# F28335_Level_Shifters.net
KiCad netlist of a schematic drawn in Altium Designer
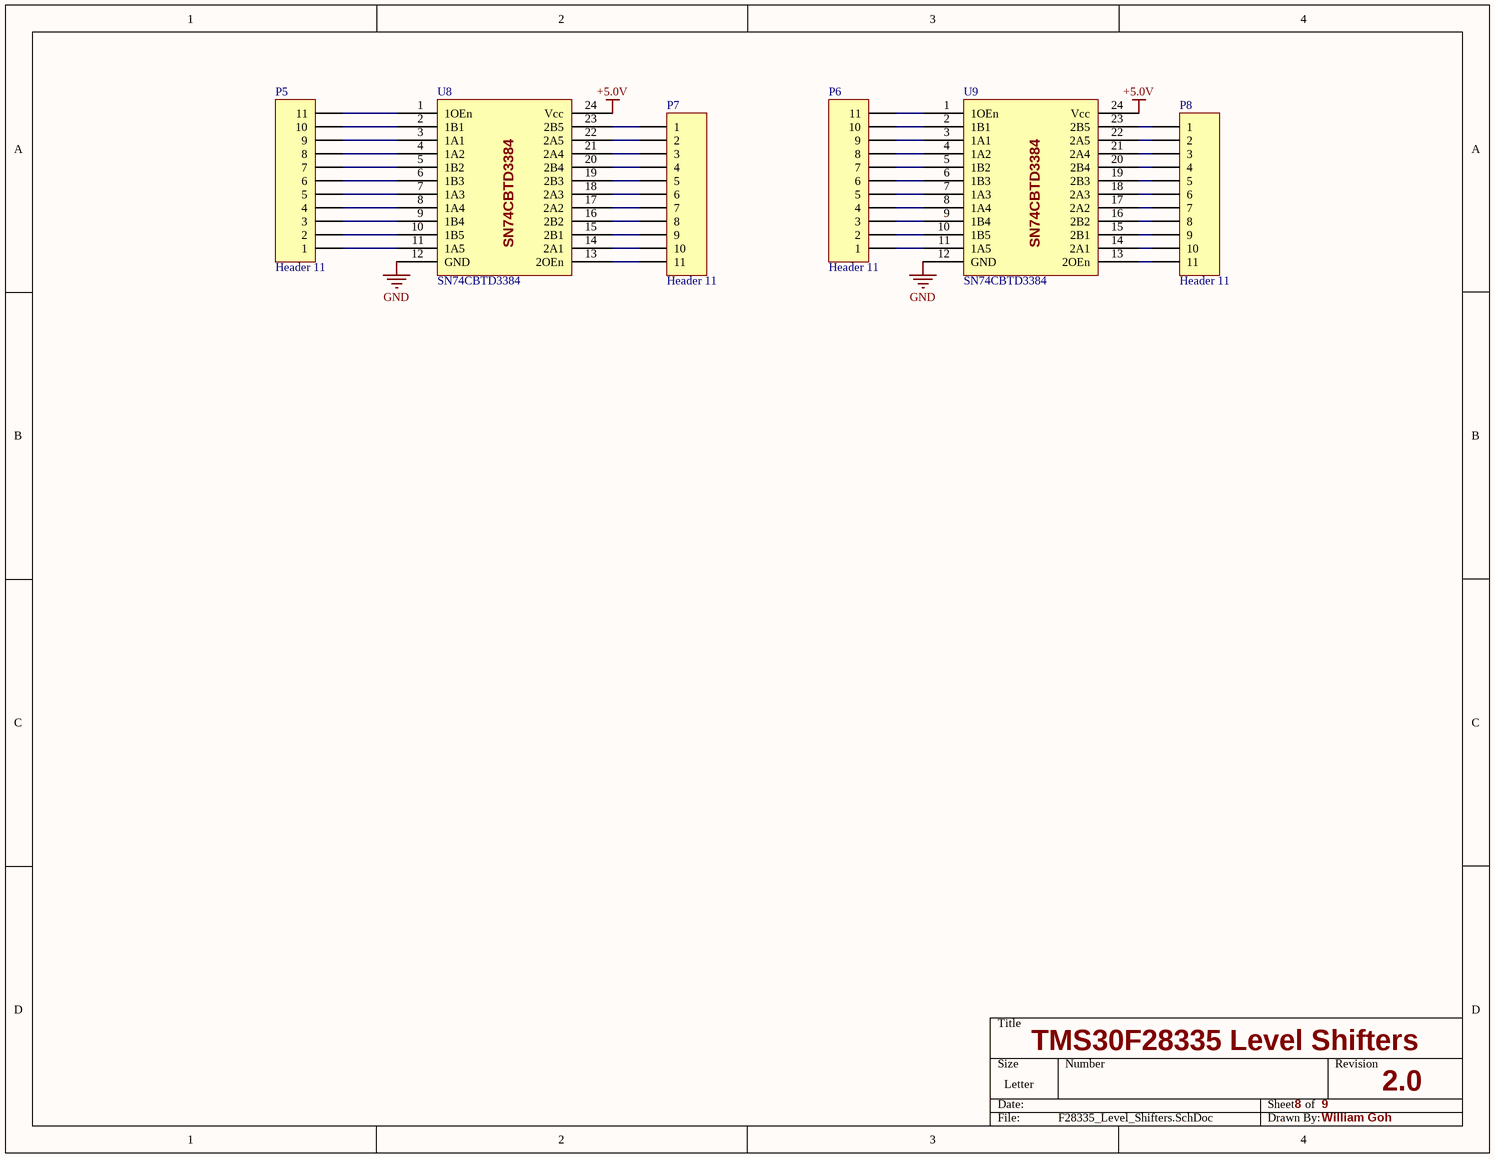
[diagram p0: F28335_Level_Shifters.SchDoc]

(export (version "E")
  (design (tool "Eeschema 10.0.6"))
  (components
    (comp (ref "P5")
      (value "Header 11")
      (footprint "HDR1X11")
      (description "Header, 11-Pin")
      (fields (field (name "PUBLISHER") "Altium Limited"))
      (libsource (lib "Miscellaneous Connectors") (part "Header 11"))
    )
    (comp (ref "P6")
      (value "Header 11")
      (footprint "HDR1X11")
      (description "Header, 11-Pin")
      (fields (field (name "PUBLISHER") "Altium Limited"))
      (libsource (lib "Miscellaneous Connectors") (part "Header 11"))
    )
    (comp (ref "P7")
      (value "Header 11")
      (footprint "HDR1X11")
      (description "Header, 11-Pin")
      (fields (field (name "PUBLISHER") "Altium Limited"))
      (libsource (lib "") (part "Header 11_1"))
    )
    (comp (ref "P8")
      (value "Header 11")
      (footprint "HDR1X11")
      (description "Header, 11-Pin")
      (fields (field (name "PUBLISHER") "Altium Limited"))
      (libsource (lib "") (part "Header 11_1"))
    )
    (comp (ref "U8")
      (value "SN74CBTD3384")
      (footprint "DW-24")
      (description "10-Bit FET Bus Switches With Level Shifting")
      (libsource (lib "F28335_DSC_Breakout") (part "SN74CBTD3384"))
    )
    (comp (ref "U9")
      (value "SN74CBTD3384")
      (footprint "DW-24")
      (description "10-Bit FET Bus Switches With Level Shifting")
      (libsource (lib "F28335_DSC_Breakout") (part "SN74CBTD3384"))
    )
  )
  (nets
    (net (code "1") (name "+5.0V") (class "Default")
      (node (ref "U8") (pin "24") (pinfunction "Vcc_24") (pintype "passive"))
      (node (ref "U9") (pin "24") (pinfunction "Vcc_24") (pintype "passive"))
    )
    (net (code "2") (name "GND") (class "Default")
      (node (ref "U8") (pin "12") (pinfunction "GND_12") (pintype "passive"))
      (node (ref "U9") (pin "12") (pinfunction "GND_12") (pintype "passive"))
    )
    (net (code "3") (name "Net-(U8-1A1)") (class "Default")
      (node (ref "P5") (pin "9") (pinfunction "9_9") (pintype "passive"))
      (node (ref "U8") (pin "3") (pinfunction "1A1_3") (pintype "passive"))
    )
    (net (code "4") (name "Net-(U8-1A2)") (class "Default")
      (node (ref "P5") (pin "8") (pinfunction "8_8") (pintype "passive"))
      (node (ref "U8") (pin "4") (pinfunction "1A2_4") (pintype "passive"))
    )
    (net (code "5") (name "Net-(U8-1A3)") (class "Default")
      (node (ref "P5") (pin "5") (pinfunction "5_5") (pintype "passive"))
      (node (ref "U8") (pin "7") (pinfunction "1A3_7") (pintype "passive"))
    )
    (net (code "6") (name "Net-(U8-1A4)") (class "Default")
      (node (ref "P5") (pin "4") (pinfunction "4_4") (pintype "passive"))
      (node (ref "U8") (pin "8") (pinfunction "1A4_8") (pintype "passive"))
    )
    (net (code "7") (name "Net-(U8-1A5)") (class "Default")
      (node (ref "P5") (pin "1") (pinfunction "1_1") (pintype "passive"))
      (node (ref "U8") (pin "11") (pinfunction "1A5_11") (pintype "passive"))
    )
    (net (code "8") (name "Net-(U8-1B1)") (class "Default")
      (node (ref "P5") (pin "10") (pinfunction "10_10") (pintype "passive"))
      (node (ref "U8") (pin "2") (pinfunction "1B1_2") (pintype "passive"))
    )
    (net (code "9") (name "Net-(U8-1B2)") (class "Default")
      (node (ref "P5") (pin "7") (pinfunction "7_7") (pintype "passive"))
      (node (ref "U8") (pin "5") (pinfunction "1B2_5") (pintype "passive"))
    )
    (net (code "10") (name "Net-(U8-1B3)") (class "Default")
      (node (ref "P5") (pin "6") (pinfunction "6_6") (pintype "passive"))
      (node (ref "U8") (pin "6") (pinfunction "1B3_6") (pintype "passive"))
    )
    (net (code "11") (name "Net-(U8-1B4)") (class "Default")
      (node (ref "P5") (pin "3") (pinfunction "3_3") (pintype "passive"))
      (node (ref "U8") (pin "9") (pinfunction "1B4_9") (pintype "passive"))
    )
    (net (code "12") (name "Net-(U8-1B5)") (class "Default")
      (node (ref "P5") (pin "2") (pinfunction "2_2") (pintype "passive"))
      (node (ref "U8") (pin "10") (pinfunction "1B5_10") (pintype "passive"))
    )
    (net (code "13") (name "Net-(U8-1OEn)") (class "Default")
      (node (ref "P5") (pin "11") (pinfunction "11_11") (pintype "passive"))
      (node (ref "U8") (pin "1") (pinfunction "1OEn_1") (pintype "passive"))
    )
    (net (code "14") (name "Net-(U8-2A1)") (class "Default")
      (node (ref "P7") (pin "10") (pinfunction "10_10") (pintype "passive"))
      (node (ref "U8") (pin "14") (pinfunction "2A1_14") (pintype "passive"))
    )
    (net (code "15") (name "Net-(U8-2A2)") (class "Default")
      (node (ref "P7") (pin "7") (pinfunction "7_7") (pintype "passive"))
      (node (ref "U8") (pin "17") (pinfunction "2A2_17") (pintype "passive"))
    )
    (net (code "16") (name "Net-(U8-2A3)") (class "Default")
      (node (ref "P7") (pin "6") (pinfunction "6_6") (pintype "passive"))
      (node (ref "U8") (pin "18") (pinfunction "2A3_18") (pintype "passive"))
    )
    (net (code "17") (name "Net-(U8-2A4)") (class "Default")
      (node (ref "P7") (pin "3") (pinfunction "3_3") (pintype "passive"))
      (node (ref "U8") (pin "21") (pinfunction "2A4_21") (pintype "passive"))
    )
    (net (code "18") (name "Net-(U8-2A5)") (class "Default")
      (node (ref "P7") (pin "2") (pinfunction "2_2") (pintype "passive"))
      (node (ref "U8") (pin "22") (pinfunction "2A5_22") (pintype "passive"))
    )
    (net (code "19") (name "Net-(U8-2B1)") (class "Default")
      (node (ref "P7") (pin "9") (pinfunction "9_9") (pintype "passive"))
      (node (ref "U8") (pin "15") (pinfunction "2B1_15") (pintype "passive"))
    )
    (net (code "20") (name "Net-(U8-2B2)") (class "Default")
      (node (ref "P7") (pin "8") (pinfunction "8_8") (pintype "passive"))
      (node (ref "U8") (pin "16") (pinfunction "2B2_16") (pintype "passive"))
    )
    (net (code "21") (name "Net-(U8-2B3)") (class "Default")
      (node (ref "P7") (pin "5") (pinfunction "5_5") (pintype "passive"))
      (node (ref "U8") (pin "19") (pinfunction "2B3_19") (pintype "passive"))
    )
    (net (code "22") (name "Net-(U8-2B4)") (class "Default")
      (node (ref "P7") (pin "4") (pinfunction "4_4") (pintype "passive"))
      (node (ref "U8") (pin "20") (pinfunction "2B4_20") (pintype "passive"))
    )
    (net (code "23") (name "Net-(U8-2B5)") (class "Default")
      (node (ref "P7") (pin "1") (pinfunction "1_1") (pintype "passive"))
      (node (ref "U8") (pin "23") (pinfunction "2B5_23") (pintype "passive"))
    )
    (net (code "24") (name "Net-(U8-2OEn)") (class "Default")
      (node (ref "P7") (pin "11") (pinfunction "11_11") (pintype "passive"))
      (node (ref "U8") (pin "13") (pinfunction "2OEn_13") (pintype "passive"))
    )
    (net (code "25") (name "Net-(U9-1A1)") (class "Default")
      (node (ref "P6") (pin "9") (pinfunction "9_9") (pintype "passive"))
      (node (ref "U9") (pin "3") (pinfunction "1A1_3") (pintype "passive"))
    )
    (net (code "26") (name "Net-(U9-1A2)") (class "Default")
      (node (ref "P6") (pin "8") (pinfunction "8_8") (pintype "passive"))
      (node (ref "U9") (pin "4") (pinfunction "1A2_4") (pintype "passive"))
    )
    (net (code "27") (name "Net-(U9-1A3)") (class "Default")
      (node (ref "P6") (pin "5") (pinfunction "5_5") (pintype "passive"))
      (node (ref "U9") (pin "7") (pinfunction "1A3_7") (pintype "passive"))
    )
    (net (code "28") (name "Net-(U9-1A4)") (class "Default")
      (node (ref "P6") (pin "4") (pinfunction "4_4") (pintype "passive"))
      (node (ref "U9") (pin "8") (pinfunction "1A4_8") (pintype "passive"))
    )
    (net (code "29") (name "Net-(U9-1A5)") (class "Default")
      (node (ref "P6") (pin "1") (pinfunction "1_1") (pintype "passive"))
      (node (ref "U9") (pin "11") (pinfunction "1A5_11") (pintype "passive"))
    )
    (net (code "30") (name "Net-(U9-1B1)") (class "Default")
      (node (ref "P6") (pin "10") (pinfunction "10_10") (pintype "passive"))
      (node (ref "U9") (pin "2") (pinfunction "1B1_2") (pintype "passive"))
    )
    (net (code "31") (name "Net-(U9-1B2)") (class "Default")
      (node (ref "P6") (pin "7") (pinfunction "7_7") (pintype "passive"))
      (node (ref "U9") (pin "5") (pinfunction "1B2_5") (pintype "passive"))
    )
    (net (code "32") (name "Net-(U9-1B3)") (class "Default")
      (node (ref "P6") (pin "6") (pinfunction "6_6") (pintype "passive"))
      (node (ref "U9") (pin "6") (pinfunction "1B3_6") (pintype "passive"))
    )
    (net (code "33") (name "Net-(U9-1B4)") (class "Default")
      (node (ref "P6") (pin "3") (pinfunction "3_3") (pintype "passive"))
      (node (ref "U9") (pin "9") (pinfunction "1B4_9") (pintype "passive"))
    )
    (net (code "34") (name "Net-(U9-1B5)") (class "Default")
      (node (ref "P6") (pin "2") (pinfunction "2_2") (pintype "passive"))
      (node (ref "U9") (pin "10") (pinfunction "1B5_10") (pintype "passive"))
    )
    (net (code "35") (name "Net-(U9-1OEn)") (class "Default")
      (node (ref "P6") (pin "11") (pinfunction "11_11") (pintype "passive"))
      (node (ref "U9") (pin "1") (pinfunction "1OEn_1") (pintype "passive"))
    )
    (net (code "36") (name "Net-(U9-2A1)") (class "Default")
      (node (ref "P8") (pin "10") (pinfunction "10_10") (pintype "passive"))
      (node (ref "U9") (pin "14") (pinfunction "2A1_14") (pintype "passive"))
    )
    (net (code "37") (name "Net-(U9-2A2)") (class "Default")
      (node (ref "P8") (pin "7") (pinfunction "7_7") (pintype "passive"))
      (node (ref "U9") (pin "17") (pinfunction "2A2_17") (pintype "passive"))
    )
    (net (code "38") (name "Net-(U9-2A3)") (class "Default")
      (node (ref "P8") (pin "6") (pinfunction "6_6") (pintype "passive"))
      (node (ref "U9") (pin "18") (pinfunction "2A3_18") (pintype "passive"))
    )
    (net (code "39") (name "Net-(U9-2A4)") (class "Default")
      (node (ref "P8") (pin "3") (pinfunction "3_3") (pintype "passive"))
      (node (ref "U9") (pin "21") (pinfunction "2A4_21") (pintype "passive"))
    )
    (net (code "40") (name "Net-(U9-2A5)") (class "Default")
      (node (ref "P8") (pin "2") (pinfunction "2_2") (pintype "passive"))
      (node (ref "U9") (pin "22") (pinfunction "2A5_22") (pintype "passive"))
    )
    (net (code "41") (name "Net-(U9-2B1)") (class "Default")
      (node (ref "P8") (pin "9") (pinfunction "9_9") (pintype "passive"))
      (node (ref "U9") (pin "15") (pinfunction "2B1_15") (pintype "passive"))
    )
    (net (code "42") (name "Net-(U9-2B2)") (class "Default")
      (node (ref "P8") (pin "8") (pinfunction "8_8") (pintype "passive"))
      (node (ref "U9") (pin "16") (pinfunction "2B2_16") (pintype "passive"))
    )
    (net (code "43") (name "Net-(U9-2B3)") (class "Default")
      (node (ref "P8") (pin "5") (pinfunction "5_5") (pintype "passive"))
      (node (ref "U9") (pin "19") (pinfunction "2B3_19") (pintype "passive"))
    )
    (net (code "44") (name "Net-(U9-2B4)") (class "Default")
      (node (ref "P8") (pin "4") (pinfunction "4_4") (pintype "passive"))
      (node (ref "U9") (pin "20") (pinfunction "2B4_20") (pintype "passive"))
    )
    (net (code "45") (name "Net-(U9-2B5)") (class "Default")
      (node (ref "P8") (pin "1") (pinfunction "1_1") (pintype "passive"))
      (node (ref "U9") (pin "23") (pinfunction "2B5_23") (pintype "passive"))
    )
    (net (code "46") (name "Net-(U9-2OEn)") (class "Default")
      (node (ref "P8") (pin "11") (pinfunction "11_11") (pintype "passive"))
      (node (ref "U9") (pin "13") (pinfunction "2OEn_13") (pintype "passive"))
    )
  )
)
